# Switch-0_8-5_5v-ds18b20-1-4Ch.net
KiCad netlist of a schematic drawn in EAGLE
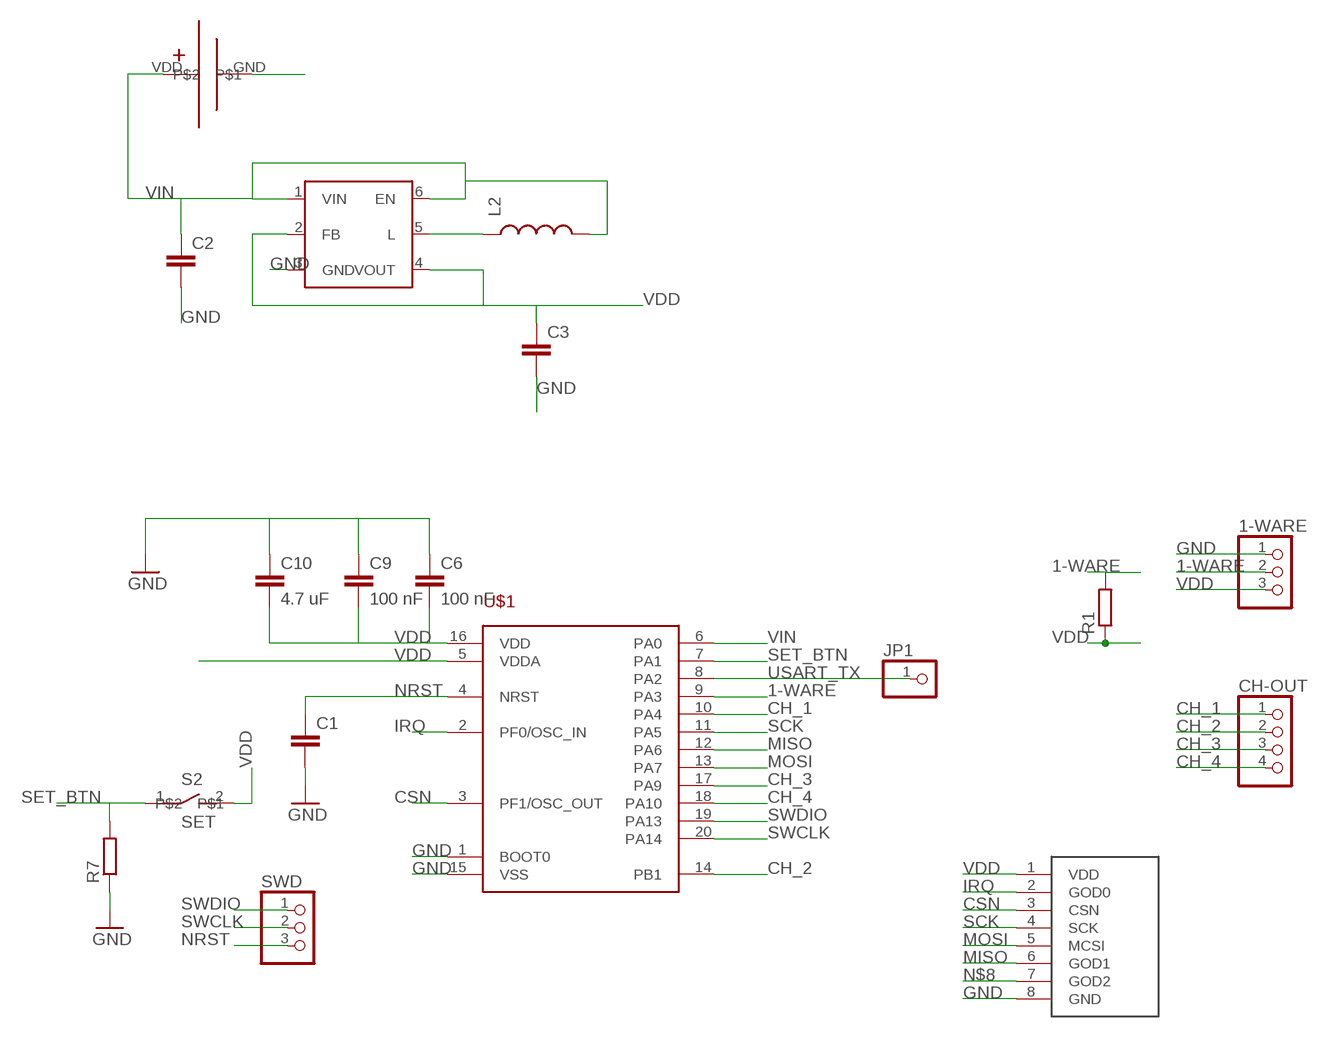
[diagram p0: schematic, sheet 1]

(export (version "E")
  (design (tool "Eeschema 10.0.6"))
  (components
    (comp (ref "1-WARE")
      (value "PINHD-1X3")
      (footprint "eagle-import:1X03")
      (libsource (lib "eagle-import") (part "pinhead_PINHD-1X3"))
    )
    (comp (ref "C1")
      (value "C-EUC0805")
      (footprint "eagle-import:C0805")
      (libsource (lib "eagle-import") (part "C-EUC0805"))
    )
    (comp (ref "C2")
      (value "C-EUC0805")
      (footprint "eagle-import:C0805")
      (libsource (lib "eagle-import") (part "C-EUC0805"))
    )
    (comp (ref "C3")
      (value "C-EUC0805")
      (footprint "eagle-import:C0805")
      (libsource (lib "eagle-import") (part "C-EUC0805"))
    )
    (comp (ref "C6")
      (value "100 nF")
      (footprint "eagle-import:C0805")
      (libsource (lib "eagle-import") (part "C-EUC0805"))
    )
    (comp (ref "C9")
      (value "100 nF")
      (footprint "eagle-import:C0805")
      (libsource (lib "eagle-import") (part "C-EUC0805"))
    )
    (comp (ref "C10")
      (value "4.7 uF")
      (footprint "eagle-import:C0805")
      (libsource (lib "eagle-import") (part "C-EUC0805"))
    )
    (comp (ref "CH-OUT")
      (value "PINHD-1X4_2.54")
      (footprint "eagle-import:1X04")
      (libsource (lib "eagle-import") (part "PINHD-1X4_2.54"))
    )
    (comp (ref "JP1")
      (value "PINHD-1X1CB")
      (footprint "eagle-import:1X01-CLEANBIG")
      (libsource (lib "eagle-import") (part "PINHD-1X1CB"))
    )
    (comp (ref "L2")
      (value "INDUCTOR1210")
      (footprint "eagle-import:1210")
      (libsource (lib "eagle-import") (part "INDUCTOR1210"))
    )
    (comp (ref "R1")
      (value "R-EU_R0805")
      (footprint "eagle-import:R0805")
      (libsource (lib "eagle-import") (part "R-EU_R0805"))
    )
    (comp (ref "R7")
      (value "R-EU_R0805")
      (footprint "eagle-import:R0805")
      (libsource (lib "eagle-import") (part "R-EU_R0805"))
    )
    (comp (ref "S2")
      (value "SET")
      (footprint "eagle-import:1210")
      (libsource (lib "eagle-import") (part "B3U"))
    )
    (comp (ref "SWD")
      (value "PINHD-1X3CB")
      (footprint "eagle-import:1X03-CLEANBIG")
      (libsource (lib "eagle-import") (part "PINHD-1X3CB"))
    )
    (comp (ref "U$1")
      (value "STM32F030F4")
      (footprint "eagle-import:TSSOP20")
      (libsource (lib "eagle-import") (part "STM32F030F4"))
    )
    (comp (ref "U$2")
      (value "TPS61221")
      (footprint "eagle-import:SC-70-6")
      (libsource (lib "eagle-import") (part "TPS6122"))
    )
    (comp (ref "U$3")
      (value "AS07-M1101S")
      (footprint "eagle-import:AS07-M1101S")
      (libsource (lib "eagle-import") (part "AS07-M1101S"))
    )
    (comp (ref "U$4")
      (value "BAT-AA1-PCB-HOLDER")
      (footprint "eagle-import:BAT-AA1-PCB-HOLDER")
      (libsource (lib "eagle-import") (part "BAT-AA1-PCB-HOLDER"))
    )
  )
  (nets
    (net (code "1") (name "/1-WARE") (class "Default")
      (node (ref "1-WARE") (pin "2") (pinfunction "2_2") (pintype "passive"))
      (node (ref "R1") (pin "2") (pinfunction "2_2") (pintype "passive"))
      (node (ref "U$1") (pin "9") (pinfunction "PA3_9") (pintype "bidirectional"))
    )
    (net (code "2") (name "/CH_1") (class "Default")
      (node (ref "CH-OUT") (pin "1") (pinfunction "1_1") (pintype "passive"))
      (node (ref "U$1") (pin "10") (pinfunction "PA4_10") (pintype "bidirectional"))
    )
    (net (code "3") (name "/CH_2") (class "Default")
      (node (ref "CH-OUT") (pin "2") (pinfunction "2_2") (pintype "passive"))
      (node (ref "U$1") (pin "14") (pinfunction "PB1_14") (pintype "bidirectional"))
    )
    (net (code "4") (name "/CH_3") (class "Default")
      (node (ref "CH-OUT") (pin "3") (pinfunction "3_3") (pintype "passive"))
      (node (ref "U$1") (pin "17") (pinfunction "PA9_17") (pintype "bidirectional"))
    )
    (net (code "5") (name "/CH_4") (class "Default")
      (node (ref "CH-OUT") (pin "4") (pinfunction "4_4") (pintype "passive"))
      (node (ref "U$1") (pin "18") (pinfunction "PA10_18") (pintype "bidirectional"))
    )
    (net (code "6") (name "/CSN") (class "Default")
      (node (ref "U$1") (pin "3") (pinfunction "PF1/OSC_OUT_3") (pintype "bidirectional"))
      (node (ref "U$3") (pin "3") (pinfunction "CSN_3") (pintype "bidirectional"))
    )
    (net (code "7") (name "/IRQ") (class "Default")
      (node (ref "U$1") (pin "2") (pinfunction "PF0/OSC_IN_2") (pintype "bidirectional"))
      (node (ref "U$3") (pin "2") (pinfunction "GOD0_2") (pintype "bidirectional"))
    )
    (net (code "8") (name "/MISO") (class "Default")
      (node (ref "U$1") (pin "12") (pinfunction "PA6_12") (pintype "bidirectional"))
      (node (ref "U$3") (pin "6") (pinfunction "GOD1_6") (pintype "bidirectional"))
    )
    (net (code "9") (name "/MOSI") (class "Default")
      (node (ref "U$1") (pin "13") (pinfunction "PA7_13") (pintype "bidirectional"))
      (node (ref "U$3") (pin "5") (pinfunction "MCSI_5") (pintype "bidirectional"))
    )
    (net (code "10") (name "/N$8") (class "Default")
      (node (ref "U$3") (pin "7") (pinfunction "GOD2_7") (pintype "bidirectional"))
    )
    (net (code "11") (name "/NRST") (class "Default")
      (node (ref "C1") (pin "1") (pinfunction "1_1") (pintype "passive"))
      (node (ref "SWD") (pin "3") (pinfunction "3_3") (pintype "passive"))
      (node (ref "U$1") (pin "4") (pinfunction "NRST_4") (pintype "bidirectional"))
    )
    (net (code "12") (name "/SCK") (class "Default")
      (node (ref "U$1") (pin "11") (pinfunction "PA5_11") (pintype "bidirectional"))
      (node (ref "U$3") (pin "4") (pinfunction "SCK_4") (pintype "bidirectional"))
    )
    (net (code "13") (name "/SET_BTN") (class "Default")
      (node (ref "R7") (pin "2") (pinfunction "2_2") (pintype "passive"))
      (node (ref "S2") (pin "1") (pinfunction "P$1_1") (pintype "power_in"))
      (node (ref "U$1") (pin "7") (pinfunction "PA1_7") (pintype "bidirectional"))
    )
    (net (code "14") (name "/SWCLK") (class "Default")
      (node (ref "SWD") (pin "2") (pinfunction "2_2") (pintype "passive"))
      (node (ref "U$1") (pin "20") (pinfunction "PA14_20") (pintype "bidirectional"))
    )
    (net (code "15") (name "/SWDIO") (class "Default")
      (node (ref "SWD") (pin "1") (pinfunction "1_1") (pintype "passive"))
      (node (ref "U$1") (pin "19") (pinfunction "PA13_19") (pintype "bidirectional"))
    )
    (net (code "16") (name "/USART_TX") (class "Default")
      (node (ref "JP1") (pin "1") (pinfunction "1_1") (pintype "passive"))
      (node (ref "U$1") (pin "8") (pinfunction "PA2_8") (pintype "bidirectional"))
    )
    (net (code "17") (name "/VDD") (class "Default")
      (node (ref "1-WARE") (pin "3") (pinfunction "3_3") (pintype "passive"))
      (node (ref "C10") (pin "2") (pinfunction "2_2") (pintype "passive"))
      (node (ref "C3") (pin "1") (pinfunction "1_1") (pintype "passive"))
      (node (ref "C6") (pin "2") (pinfunction "2_2") (pintype "passive"))
      (node (ref "C9") (pin "2") (pinfunction "2_2") (pintype "passive"))
      (node (ref "R1") (pin "1") (pinfunction "1_1") (pintype "passive"))
      (node (ref "S2") (pin "2") (pinfunction "P$2_2") (pintype "power_in"))
      (node (ref "U$1") (pin "16") (pinfunction "VDD_16") (pintype "bidirectional"))
      (node (ref "U$1") (pin "5") (pinfunction "VDDA_5") (pintype "bidirectional"))
      (node (ref "U$2") (pin "2") (pinfunction "FB_2") (pintype "bidirectional"))
      (node (ref "U$2") (pin "4") (pinfunction "VOUT_4") (pintype "bidirectional"))
      (node (ref "U$3") (pin "1") (pinfunction "VDD_1") (pintype "bidirectional"))
    )
    (net (code "18") (name "/VIN") (class "Default")
      (node (ref "C2") (pin "1") (pinfunction "1_1") (pintype "passive"))
      (node (ref "L2") (pin "2") (pinfunction "2_2") (pintype "passive"))
      (node (ref "U$1") (pin "6") (pinfunction "PA0_6") (pintype "bidirectional"))
      (node (ref "U$2") (pin "1") (pinfunction "VIN_1") (pintype "bidirectional"))
      (node (ref "U$2") (pin "6") (pinfunction "EN_6") (pintype "bidirectional"))
      (node (ref "U$4") (pin "VDD") (pinfunction "P$1_VDD") (pintype "bidirectional"))
    )
    (net (code "19") (name "GND") (class "Default")
      (node (ref "1-WARE") (pin "1") (pinfunction "1_1") (pintype "passive"))
      (node (ref "C1") (pin "2") (pinfunction "2_2") (pintype "passive"))
      (node (ref "C10") (pin "1") (pinfunction "1_1") (pintype "passive"))
      (node (ref "C2") (pin "2") (pinfunction "2_2") (pintype "passive"))
      (node (ref "C3") (pin "2") (pinfunction "2_2") (pintype "passive"))
      (node (ref "C6") (pin "1") (pinfunction "1_1") (pintype "passive"))
      (node (ref "C9") (pin "1") (pinfunction "1_1") (pintype "passive"))
      (node (ref "R7") (pin "1") (pinfunction "1_1") (pintype "passive"))
      (node (ref "U$1") (pin "1") (pinfunction "BOOT0_1") (pintype "bidirectional"))
      (node (ref "U$1") (pin "15") (pinfunction "VSS_15") (pintype "bidirectional"))
      (node (ref "U$2") (pin "3") (pinfunction "GND_3") (pintype "bidirectional"))
      (node (ref "U$3") (pin "8") (pinfunction "GND_8") (pintype "bidirectional"))
      (node (ref "U$4") (pin "GND") (pinfunction "P$2_GND") (pintype "bidirectional"))
    )
    (net (code "20") (name "Net-(U$2-L)") (class "Default")
      (node (ref "L2") (pin "1") (pinfunction "1_1") (pintype "passive"))
      (node (ref "U$2") (pin "5") (pinfunction "L_5") (pintype "bidirectional"))
    )
  )
)
